# SparkFun_ProtoShield_Kit_rev31.net
KiCad netlist of a schematic drawn in EAGLE
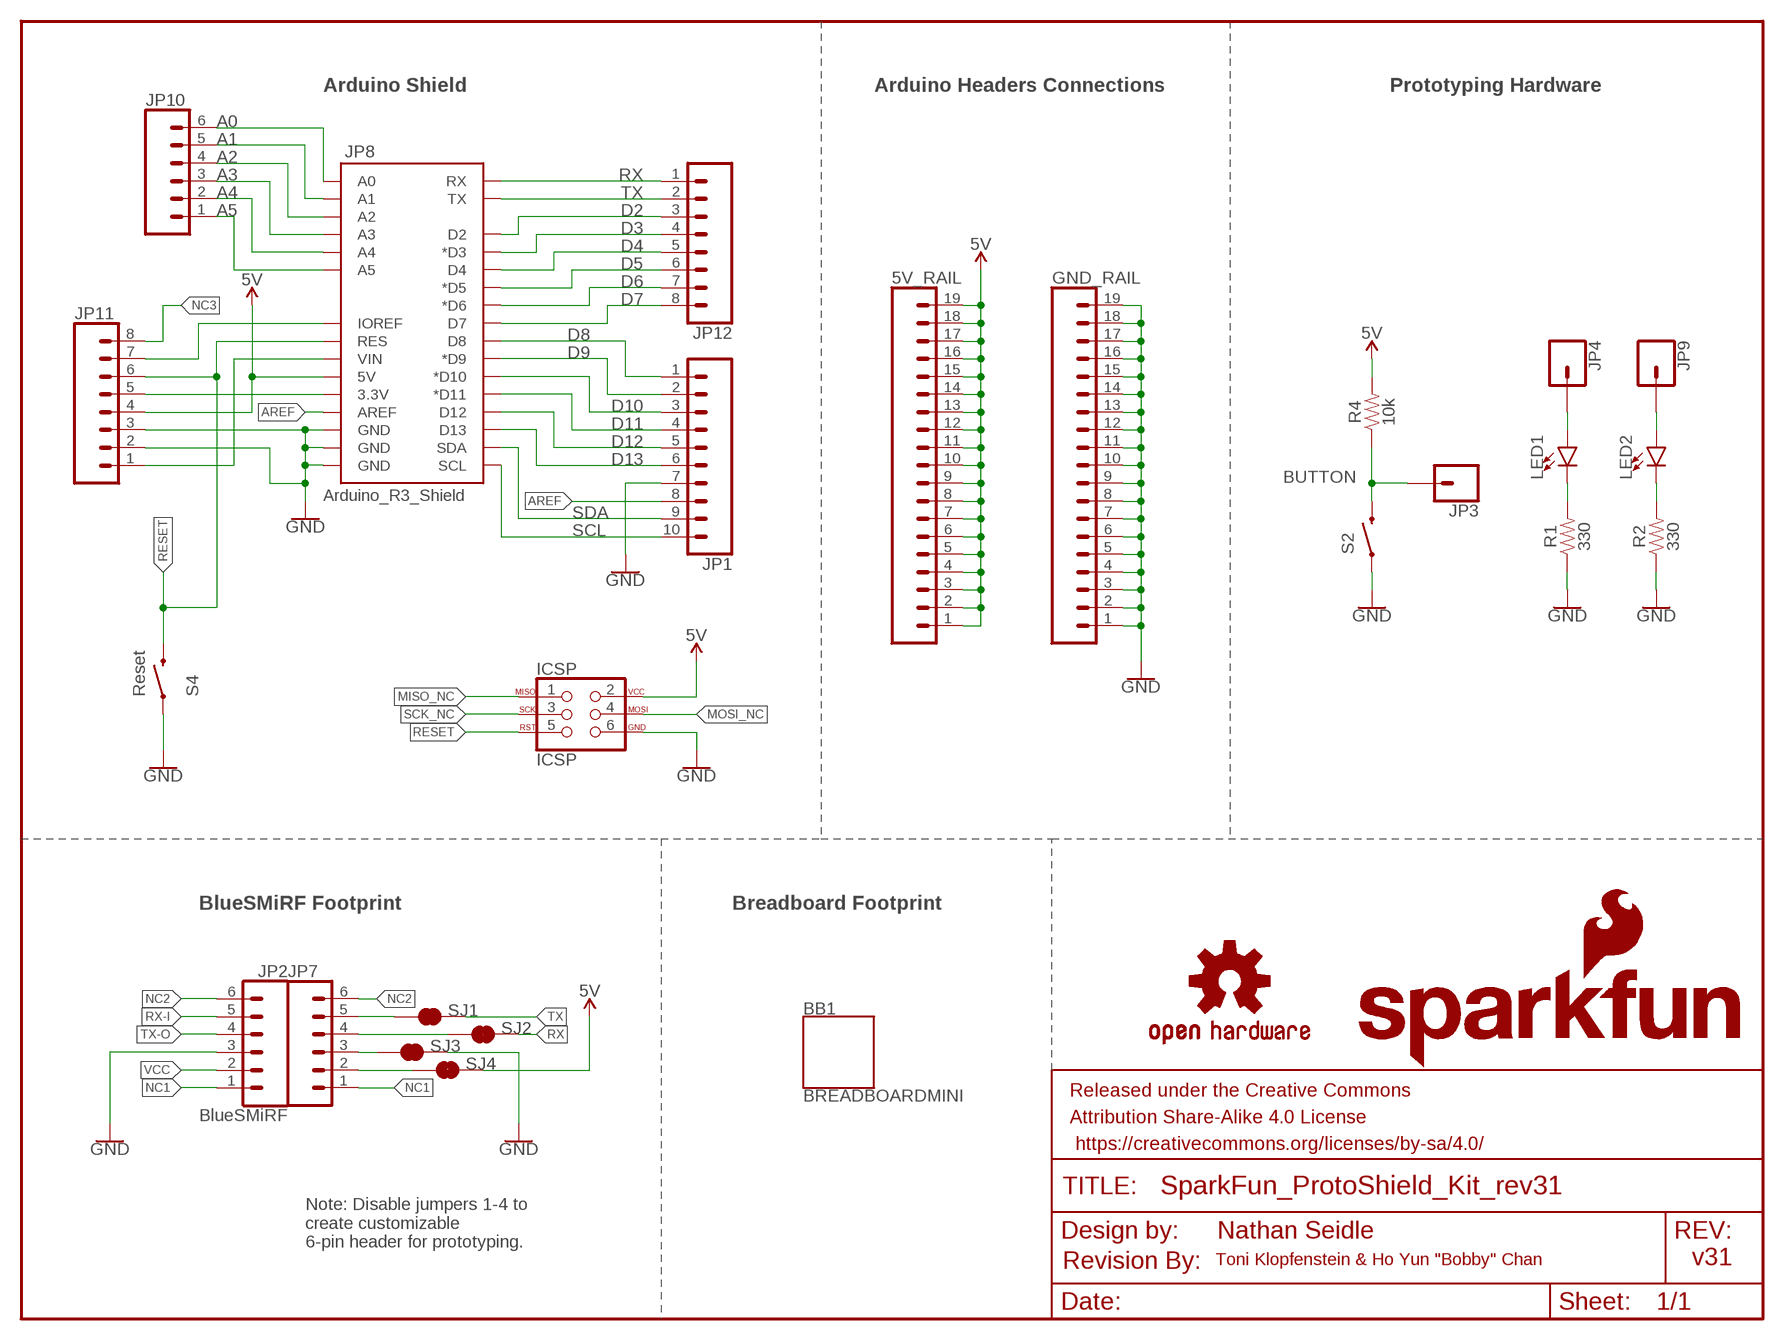
[diagram p0: schematic, sheet 1]

(export (version "E")
  (design (tool "Eeschema 10.0.6"))
  (components
    (comp (ref "5V_RAIL")
      (value "CONN_19")
      (footprint "eagle-import:1X19")
      (libsource (lib "eagle-import") (part "CONN_19"))
    )
    (comp (ref "BB1")
      (value "BREADBOARDMINI")
      (footprint "eagle-import:BREADBOARD-MINI")
      (libsource (lib "eagle-import") (part "BREADBOARDMINI"))
    )
    (comp (ref "FRAME1")
      (value "FRAME-LETTER")
      (footprint "eagle-import:CREATIVE_COMMONS")
      (libsource (lib "eagle-import") (part "FRAME-LETTER"))
    )
    (comp (ref "GND_RAIL")
      (value "CONN_19")
      (footprint "eagle-import:1X19")
      (libsource (lib "eagle-import") (part "CONN_19"))
    )
    (comp (ref "ICSP")
      (value "ICSP")
      (footprint "eagle-import:2X3")
      (libsource (lib "eagle-import") (part "AVR_SPI_PROG_3X2PTH"))
    )
    (comp (ref "JP1")
      (value "CONN_10\"")
      (footprint "eagle-import:1X10")
      (libsource (lib "eagle-import") (part "CONN_10{dblquote}"))
    )
    (comp (ref "JP2")
      (value "BlueSMiRF")
      (footprint "eagle-import:1X06")
      (libsource (lib "eagle-import") (part "CONN_06SILK_FEMALE_PTH"))
    )
    (comp (ref "JP3")
      (value "CONN_01")
      (footprint "eagle-import:1X01")
      (libsource (lib "eagle-import") (part "CONN_01"))
    )
    (comp (ref "JP4")
      (value "CONN_01")
      (footprint "eagle-import:1X01")
      (libsource (lib "eagle-import") (part "CONN_01"))
    )
    (comp (ref "JP7")
      (value "CONN_06SILK_FEMALE_PTH")
      (footprint "eagle-import:1X06")
      (libsource (lib "eagle-import") (part "CONN_06SILK_FEMALE_PTH"))
    )
    (comp (ref "JP8")
      (value "ARDUINO_R3_SHIELDR3_PROTO_SHIELD")
      (footprint "eagle-import:UNO_R3_PROTO_SHIELD")
      (libsource (lib "eagle-import") (part "ARDUINO_R3_SHIELDR3_PROTO_SHIELD"))
    )
    (comp (ref "JP9")
      (value "CONN_01")
      (footprint "eagle-import:1X01")
      (libsource (lib "eagle-import") (part "CONN_01"))
    )
    (comp (ref "JP10")
      (value "CONN_06SILK_FEMALE_PTH")
      (footprint "eagle-import:1X06")
      (libsource (lib "eagle-import") (part "CONN_06SILK_FEMALE_PTH"))
    )
    (comp (ref "JP11")
      (value "CONN_08\"")
      (footprint "eagle-import:1X08")
      (libsource (lib "eagle-import") (part "CONN_08{dblquote}"))
    )
    (comp (ref "JP12")
      (value "CONN_08\"")
      (footprint "eagle-import:1X08")
      (libsource (lib "eagle-import") (part "CONN_08{dblquote}"))
    )
    (comp (ref "LED1")
      (value "LED3MM")
      (footprint "eagle-import:LED_3MM")
      (libsource (lib "eagle-import") (part "LED3MM"))
    )
    (comp (ref "LED2")
      (value "LED3MM")
      (footprint "eagle-import:LED_3MM")
      (libsource (lib "eagle-import") (part "LED3MM"))
    )
    (comp (ref "LOGO1")
      (value "OSHW-LOGOS")
      (footprint "eagle-import:OSHW-LOGO-S")
      (libsource (lib "eagle-import") (part "OSHW-LOGOS"))
    )
    (comp (ref "R1")
      (value "330")
      (footprint "eagle-import:AXIAL-0.3")
      (libsource (lib "eagle-import") (part "330OHM-HORIZ-1/10W-5%"))
    )
    (comp (ref "R2")
      (value "330")
      (footprint "eagle-import:AXIAL-0.3")
      (libsource (lib "eagle-import") (part "330OHM-HORIZ-1/10W-5%"))
    )
    (comp (ref "R4")
      (value "10k")
      (footprint "eagle-import:AXIAL-0.3")
      (libsource (lib "eagle-import") (part "10KOHM-HORIZ-1/4W-5%"))
    )
    (comp (ref "S2")
      (value "MOMENTARY-SWITCH-SPST-PTH-6.0MM-KIT")
      (footprint "eagle-import:TACTILE_SWITCH_PTH_6.0MM_KIT")
      (libsource (lib "eagle-import") (part "MOMENTARY-SWITCH-SPST-PTH-6.0MM-KIT"))
    )
    (comp (ref "S4")
      (value "MOMENTARY-SWITCH-SPST-PTH-6.0MM-KIT")
      (footprint "eagle-import:TACTILE_SWITCH_PTH_6.0MM_KIT")
      (libsource (lib "eagle-import") (part "MOMENTARY-SWITCH-SPST-PTH-6.0MM-KIT"))
    )
    (comp (ref "SJ1")
      (value "JUMPER-SMT_2_NC_TRACE_SILK")
      (footprint "eagle-import:SMT-JUMPER_2_NC_TRACE_SILK")
      (libsource (lib "eagle-import") (part "JUMPER-SMT_2_NC_TRACE_SILK"))
    )
    (comp (ref "SJ2")
      (value "JUMPER-SMT_2_NC_TRACE_SILK")
      (footprint "eagle-import:SMT-JUMPER_2_NC_TRACE_SILK")
      (libsource (lib "eagle-import") (part "JUMPER-SMT_2_NC_TRACE_SILK"))
    )
    (comp (ref "SJ3")
      (value "JUMPER-SMT_2_NC_TRACE_SILK")
      (footprint "eagle-import:SMT-JUMPER_2_NC_TRACE_SILK")
      (libsource (lib "eagle-import") (part "JUMPER-SMT_2_NC_TRACE_SILK"))
    )
    (comp (ref "SJ4")
      (value "JUMPER-SMT_2_NC_TRACE_SILK")
      (footprint "eagle-import:SMT-JUMPER_2_NC_TRACE_SILK")
      (libsource (lib "eagle-import") (part "JUMPER-SMT_2_NC_TRACE_SILK"))
    )
    (comp (ref "U$1")
      (value "SFE_LOGO_NAME_FLAME.1_INCH")
      (footprint "eagle-import:SFE_LOGO_NAME_FLAME_.1")
      (libsource (lib "eagle-import") (part "SFE_LOGO_NAME_FLAME.1_INCH"))
    )
    (comp (ref "U$2")
      (value "REVISION")
      (footprint "eagle-import:REVISION")
      (libsource (lib "eagle-import") (part "REVISION"))
    )
  )
  (nets
    (net (code "1") (name "/BUTTON") (class "Default")
      (node (ref "JP3") (pin "1") (pinfunction "1_1") (pintype "passive"))
      (node (ref "R4") (pin "P$1") (pinfunction "1_P$1") (pintype "passive"))
      (node (ref "S2") (pin "3") (pinfunction "2_3") (pintype "passive"))
    )
    (net (code "2") (name "/D2") (class "Default")
      (node (ref "JP12") (pin "3") (pinfunction "3_3") (pintype "passive"))
      (node (ref "JP8") (pin "D2") (pinfunction "D2_D2") (pintype "bidirectional"))
    )
    (net (code "3") (name "/D3") (class "Default")
      (node (ref "JP12") (pin "4") (pinfunction "4_4") (pintype "passive"))
      (node (ref "JP8") (pin "D3") (pinfunction "*D3_D3") (pintype "bidirectional"))
    )
    (net (code "4") (name "/D4") (class "Default")
      (node (ref "JP12") (pin "5") (pinfunction "5_5") (pintype "passive"))
      (node (ref "JP8") (pin "D4") (pinfunction "D4_D4") (pintype "bidirectional"))
    )
    (net (code "5") (name "/D5") (class "Default")
      (node (ref "JP12") (pin "6") (pinfunction "6_6") (pintype "passive"))
      (node (ref "JP8") (pin "D5") (pinfunction "*D5_D5") (pintype "bidirectional"))
    )
    (net (code "6") (name "/D6") (class "Default")
      (node (ref "JP12") (pin "7") (pinfunction "7_7") (pintype "passive"))
      (node (ref "JP8") (pin "D6") (pinfunction "*D6_D6") (pintype "bidirectional"))
    )
    (net (code "7") (name "/D7") (class "Default")
      (node (ref "JP12") (pin "8") (pinfunction "8_8") (pintype "passive"))
      (node (ref "JP8") (pin "D7") (pinfunction "D7_D7") (pintype "bidirectional"))
    )
    (net (code "8") (name "/D8") (class "Default")
      (node (ref "JP1") (pin "1") (pinfunction "1_1") (pintype "passive"))
      (node (ref "JP8") (pin "D8") (pinfunction "D8_D8") (pintype "bidirectional"))
    )
    (net (code "9") (name "/D9") (class "Default")
      (node (ref "JP1") (pin "2") (pinfunction "2_2") (pintype "passive"))
      (node (ref "JP8") (pin "D9") (pinfunction "*D9_D9") (pintype "bidirectional"))
    )
    (net (code "10") (name "/D10") (class "Default")
      (node (ref "JP1") (pin "3") (pinfunction "3_3") (pintype "passive"))
      (node (ref "JP8") (pin "D10") (pinfunction "*D10_D10") (pintype "bidirectional"))
    )
    (net (code "11") (name "/D11") (class "Default")
      (node (ref "JP1") (pin "4") (pinfunction "4_4") (pintype "passive"))
      (node (ref "JP8") (pin "D11") (pinfunction "*D11_D11") (pintype "bidirectional"))
    )
    (net (code "12") (name "/D12") (class "Default")
      (node (ref "JP1") (pin "5") (pinfunction "5_5") (pintype "passive"))
      (node (ref "JP8") (pin "D12") (pinfunction "D12_D12") (pintype "bidirectional"))
    )
    (net (code "13") (name "/D13") (class "Default")
      (node (ref "JP1") (pin "6") (pinfunction "6_6") (pintype "passive"))
      (node (ref "JP8") (pin "D13") (pinfunction "D13_D13") (pintype "bidirectional"))
    )
    (net (code "14") (name "/SCL") (class "Default")
      (node (ref "JP1") (pin "10") (pinfunction "10_10") (pintype "passive"))
      (node (ref "JP8") (pin "SCL") (pinfunction "SCL_SCL") (pintype "bidirectional"))
    )
    (net (code "15") (name "/SDA") (class "Default")
      (node (ref "JP1") (pin "9") (pinfunction "9_9") (pintype "passive"))
      (node (ref "JP8") (pin "SDA") (pinfunction "SDA_SDA") (pintype "bidirectional"))
    )
    (net (code "16") (name "5V") (class "Default")
      (node (ref "5V_RAIL") (pin "1") (pinfunction "1_1") (pintype "passive"))
      (node (ref "5V_RAIL") (pin "10") (pinfunction "10_10") (pintype "passive"))
      (node (ref "5V_RAIL") (pin "11") (pinfunction "11_11") (pintype "passive"))
      (node (ref "5V_RAIL") (pin "12") (pinfunction "12_12") (pintype "passive"))
      (node (ref "5V_RAIL") (pin "13") (pinfunction "13_13") (pintype "passive"))
      (node (ref "5V_RAIL") (pin "14") (pinfunction "14_14") (pintype "passive"))
      (node (ref "5V_RAIL") (pin "15") (pinfunction "15_15") (pintype "passive"))
      (node (ref "5V_RAIL") (pin "16") (pinfunction "16_16") (pintype "passive"))
      (node (ref "5V_RAIL") (pin "17") (pinfunction "17_17") (pintype "passive"))
      (node (ref "5V_RAIL") (pin "18") (pinfunction "18_18") (pintype "passive"))
      (node (ref "5V_RAIL") (pin "19") (pinfunction "19_19") (pintype "passive"))
      (node (ref "5V_RAIL") (pin "2") (pinfunction "2_2") (pintype "passive"))
      (node (ref "5V_RAIL") (pin "3") (pinfunction "3_3") (pintype "passive"))
      (node (ref "5V_RAIL") (pin "4") (pinfunction "4_4") (pintype "passive"))
      (node (ref "5V_RAIL") (pin "5") (pinfunction "5_5") (pintype "passive"))
      (node (ref "5V_RAIL") (pin "6") (pinfunction "6_6") (pintype "passive"))
      (node (ref "5V_RAIL") (pin "7") (pinfunction "7_7") (pintype "passive"))
      (node (ref "5V_RAIL") (pin "8") (pinfunction "8_8") (pintype "passive"))
      (node (ref "5V_RAIL") (pin "9") (pinfunction "9_9") (pintype "passive"))
      (node (ref "ICSP") (pin "2") (pinfunction "2_2") (pintype "passive"))
      (node (ref "JP11") (pin "4") (pinfunction "4_4") (pintype "passive"))
      (node (ref "JP8") (pin "5V") (pinfunction "5V_5V") (pintype "bidirectional"))
      (node (ref "R4") (pin "P$2") (pinfunction "2_P$2") (pintype "passive"))
      (node (ref "SJ4") (pin "2") (pinfunction "2_2") (pintype "passive"))
    )
    (net (code "17") (name "AREF") (class "Default")
      (node (ref "JP1") (pin "8") (pinfunction "8_8") (pintype "passive"))
      (node (ref "JP8") (pin "AREF") (pinfunction "AREF_AREF") (pintype "bidirectional"))
    )
    (net (code "18") (name "GND") (class "Default")
      (node (ref "GND_RAIL") (pin "1") (pinfunction "1_1") (pintype "passive"))
      (node (ref "GND_RAIL") (pin "10") (pinfunction "10_10") (pintype "passive"))
      (node (ref "GND_RAIL") (pin "11") (pinfunction "11_11") (pintype "passive"))
      (node (ref "GND_RAIL") (pin "12") (pinfunction "12_12") (pintype "passive"))
      (node (ref "GND_RAIL") (pin "13") (pinfunction "13_13") (pintype "passive"))
      (node (ref "GND_RAIL") (pin "14") (pinfunction "14_14") (pintype "passive"))
      (node (ref "GND_RAIL") (pin "15") (pinfunction "15_15") (pintype "passive"))
      (node (ref "GND_RAIL") (pin "16") (pinfunction "16_16") (pintype "passive"))
      (node (ref "GND_RAIL") (pin "17") (pinfunction "17_17") (pintype "passive"))
      (node (ref "GND_RAIL") (pin "18") (pinfunction "18_18") (pintype "passive"))
      (node (ref "GND_RAIL") (pin "19") (pinfunction "19_19") (pintype "passive"))
      (node (ref "GND_RAIL") (pin "2") (pinfunction "2_2") (pintype "passive"))
      (node (ref "GND_RAIL") (pin "3") (pinfunction "3_3") (pintype "passive"))
      (node (ref "GND_RAIL") (pin "4") (pinfunction "4_4") (pintype "passive"))
      (node (ref "GND_RAIL") (pin "5") (pinfunction "5_5") (pintype "passive"))
      (node (ref "GND_RAIL") (pin "6") (pinfunction "6_6") (pintype "passive"))
      (node (ref "GND_RAIL") (pin "7") (pinfunction "7_7") (pintype "passive"))
      (node (ref "GND_RAIL") (pin "8") (pinfunction "8_8") (pintype "passive"))
      (node (ref "GND_RAIL") (pin "9") (pinfunction "9_9") (pintype "passive"))
      (node (ref "ICSP") (pin "6") (pinfunction "6_6") (pintype "passive"))
      (node (ref "JP1") (pin "7") (pinfunction "7_7") (pintype "passive"))
      (node (ref "JP11") (pin "2") (pinfunction "2_2") (pintype "passive"))
      (node (ref "JP11") (pin "3") (pinfunction "3_3") (pintype "passive"))
      (node (ref "JP2") (pin "3") (pinfunction "3_3") (pintype "passive"))
      (node (ref "JP7") (pin "3") (pinfunction "3_3") (pintype "passive"))
      (node (ref "JP8") (pin "GND@0") (pinfunction "GND_GND@0") (pintype "bidirectional"))
      (node (ref "JP8") (pin "GND@1") (pinfunction "GND_GND@1") (pintype "bidirectional"))
      (node (ref "JP8") (pin "GND@2") (pinfunction "GND_GND@2") (pintype "bidirectional"))
      (node (ref "R1") (pin "P$1") (pinfunction "1_P$1") (pintype "passive"))
      (node (ref "R2") (pin "P$1") (pinfunction "1_P$1") (pintype "passive"))
      (node (ref "S2") (pin "1") (pinfunction "1_1") (pintype "passive"))
      (node (ref "S4") (pin "1") (pinfunction "1_1") (pintype "passive"))
      (node (ref "SJ3") (pin "1") (pinfunction "1_1") (pintype "passive"))
      (node (ref "SJ3") (pin "2") (pinfunction "2_2") (pintype "passive"))
    )
    (net (code "19") (name "MISO_NC") (class "Default")
      (node (ref "ICSP") (pin "1") (pinfunction "1_1") (pintype "passive"))
    )
    (net (code "20") (name "MOSI_NC") (class "Default")
      (node (ref "ICSP") (pin "4") (pinfunction "4_4") (pintype "passive"))
    )
    (net (code "21") (name "NC1") (class "Default")
      (node (ref "JP2") (pin "1") (pinfunction "1_1") (pintype "passive"))
      (node (ref "JP7") (pin "1") (pinfunction "1_1") (pintype "passive"))
    )
    (net (code "22") (name "NC2") (class "Default")
      (node (ref "JP2") (pin "6") (pinfunction "6_6") (pintype "passive"))
      (node (ref "JP7") (pin "6") (pinfunction "6_6") (pintype "passive"))
    )
    (net (code "23") (name "NC3") (class "Default")
      (node (ref "JP11") (pin "8") (pinfunction "8_8") (pintype "passive"))
    )
    (net (code "24") (name "Net-(JP4-Pad1)") (class "Default")
      (node (ref "JP4") (pin "1") (pinfunction "1_1") (pintype "passive"))
      (node (ref "LED1") (pin "A") (pinfunction "A_A") (pintype "passive"))
    )
    (net (code "25") (name "Net-(JP9-Pad1)") (class "Default")
      (node (ref "JP9") (pin "1") (pinfunction "1_1") (pintype "passive"))
      (node (ref "LED2") (pin "A") (pinfunction "A_A") (pintype "passive"))
    )
    (net (code "26") (name "Net-(JP10-Pad1)") (class "Default")
      (node (ref "JP10") (pin "1") (pinfunction "1_1") (pintype "passive"))
      (node (ref "JP8") (pin "A5") (pinfunction "A5_A5") (pintype "bidirectional"))
    )
    (net (code "27") (name "Net-(JP10-Pad2)") (class "Default")
      (node (ref "JP10") (pin "2") (pinfunction "2_2") (pintype "passive"))
      (node (ref "JP8") (pin "A4") (pinfunction "A4_A4") (pintype "bidirectional"))
    )
    (net (code "28") (name "Net-(JP10-Pad3)") (class "Default")
      (node (ref "JP10") (pin "3") (pinfunction "3_3") (pintype "passive"))
      (node (ref "JP8") (pin "A3") (pinfunction "A3_A3") (pintype "bidirectional"))
    )
    (net (code "29") (name "Net-(JP10-Pad4)") (class "Default")
      (node (ref "JP10") (pin "4") (pinfunction "4_4") (pintype "passive"))
      (node (ref "JP8") (pin "A2") (pinfunction "A2_A2") (pintype "bidirectional"))
    )
    (net (code "30") (name "Net-(JP10-Pad5)") (class "Default")
      (node (ref "JP10") (pin "5") (pinfunction "5_5") (pintype "passive"))
      (node (ref "JP8") (pin "A1") (pinfunction "A1_A1") (pintype "bidirectional"))
    )
    (net (code "31") (name "Net-(JP10-Pad6)") (class "Default")
      (node (ref "JP10") (pin "6") (pinfunction "6_6") (pintype "passive"))
      (node (ref "JP8") (pin "A0") (pinfunction "A0_A0") (pintype "bidirectional"))
    )
    (net (code "32") (name "Net-(JP11-Pad1)") (class "Default")
      (node (ref "JP11") (pin "1") (pinfunction "1_1") (pintype "passive"))
      (node (ref "JP8") (pin "VIN") (pinfunction "VIN_VIN") (pintype "bidirectional"))
    )
    (net (code "33") (name "Net-(JP11-Pad5)") (class "Default")
      (node (ref "JP11") (pin "5") (pinfunction "5_5") (pintype "passive"))
      (node (ref "JP8") (pin "3.3V") (pinfunction "3.3V_3.3V") (pintype "bidirectional"))
    )
    (net (code "34") (name "Net-(JP11-Pad7)") (class "Default")
      (node (ref "JP11") (pin "7") (pinfunction "7_7") (pintype "passive"))
      (node (ref "JP8") (pin "IOREF") (pinfunction "IOREF_IOREF") (pintype "bidirectional"))
    )
    (net (code "35") (name "Net-(LED1-C)") (class "Default")
      (node (ref "LED1") (pin "K") (pinfunction "C_K") (pintype "passive"))
      (node (ref "R1") (pin "P$2") (pinfunction "2_P$2") (pintype "passive"))
    )
    (net (code "36") (name "Net-(LED2-C)") (class "Default")
      (node (ref "LED2") (pin "K") (pinfunction "C_K") (pintype "passive"))
      (node (ref "R2") (pin "P$2") (pinfunction "2_P$2") (pintype "passive"))
    )
    (net (code "37") (name "RESET") (class "Default")
      (node (ref "ICSP") (pin "5") (pinfunction "5_5") (pintype "passive"))
      (node (ref "JP11") (pin "6") (pinfunction "6_6") (pintype "passive"))
      (node (ref "JP8") (pin "RES") (pinfunction "RES_RES") (pintype "bidirectional"))
      (node (ref "S4") (pin "3") (pinfunction "2_3") (pintype "passive"))
    )
    (net (code "38") (name "RX") (class "Default")
      (node (ref "JP12") (pin "1") (pinfunction "1_1") (pintype "passive"))
      (node (ref "JP8") (pin "RX") (pinfunction "RX_RX") (pintype "bidirectional"))
      (node (ref "SJ2") (pin "2") (pinfunction "2_2") (pintype "passive"))
    )
    (net (code "39") (name "RX-I") (class "Default")
      (node (ref "JP2") (pin "5") (pinfunction "5_5") (pintype "passive"))
      (node (ref "JP7") (pin "5") (pinfunction "5_5") (pintype "passive"))
      (node (ref "SJ1") (pin "1") (pinfunction "1_1") (pintype "passive"))
    )
    (net (code "40") (name "SCK_NC") (class "Default")
      (node (ref "ICSP") (pin "3") (pinfunction "3_3") (pintype "passive"))
    )
    (net (code "41") (name "TX") (class "Default")
      (node (ref "JP12") (pin "2") (pinfunction "2_2") (pintype "passive"))
      (node (ref "JP8") (pin "TX") (pinfunction "TX_TX") (pintype "bidirectional"))
      (node (ref "SJ1") (pin "2") (pinfunction "2_2") (pintype "passive"))
    )
    (net (code "42") (name "TX-O") (class "Default")
      (node (ref "JP2") (pin "4") (pinfunction "4_4") (pintype "passive"))
      (node (ref "JP7") (pin "4") (pinfunction "4_4") (pintype "passive"))
      (node (ref "SJ2") (pin "1") (pinfunction "1_1") (pintype "passive"))
    )
    (net (code "43") (name "VCC") (class "Default")
      (node (ref "JP2") (pin "2") (pinfunction "2_2") (pintype "passive"))
      (node (ref "JP7") (pin "2") (pinfunction "2_2") (pintype "passive"))
      (node (ref "SJ4") (pin "1") (pinfunction "1_1") (pintype "passive"))
    )
  )
)
